# Serial_Keyboard_one.net
KiCad netlist of a schematic drawn in EAGLE
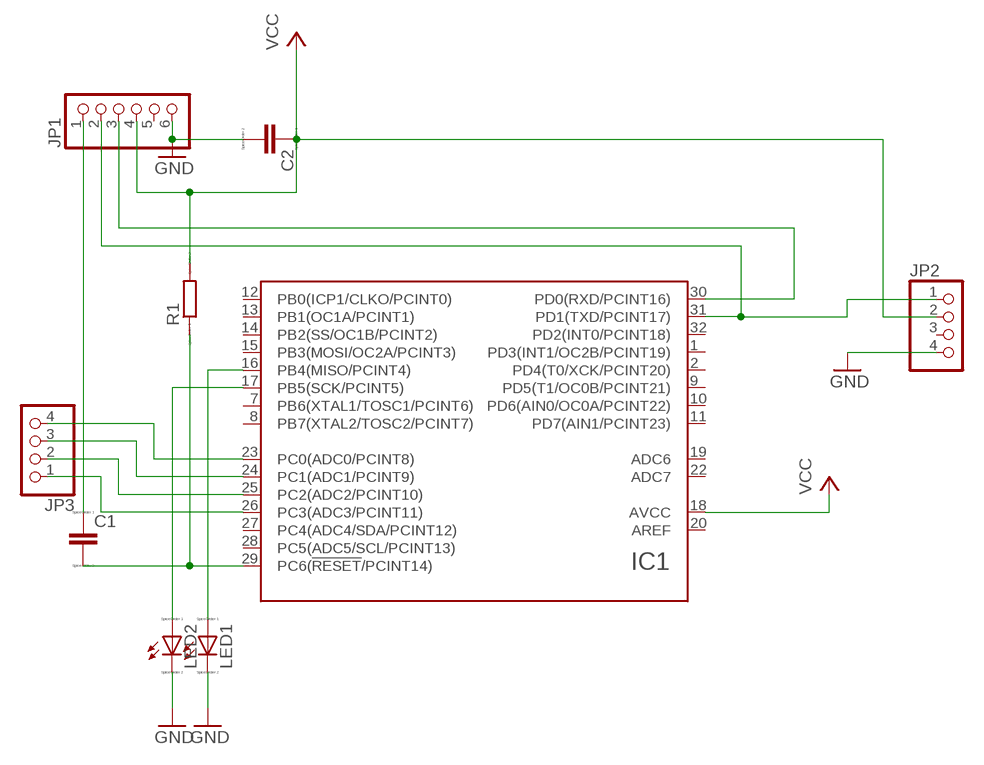
[diagram p0: schematic, sheet 1]

(export (version "E")
  (design (tool "Eeschema 10.0.6"))
  (components
    (comp (ref "C1")
      (value "CC0603")
      (footprint "eagle-import:C0603")
      (libsource (lib "eagle-import") (part "CC0603"))
    )
    (comp (ref "C2")
      (value "CC0603")
      (footprint "eagle-import:C0603")
      (libsource (lib "eagle-import") (part "CC0603"))
    )
    (comp (ref "IC1")
      (value "ATMEGA48/88/168/328-AU")
      (footprint "eagle-import:TQFP32-08")
      (libsource (lib "eagle-import") (part "ATMEGA48/88/168/328-AU"))
    )
    (comp (ref "JP1")
      (value "PINHD-1X6")
      (footprint "eagle-import:1X06")
      (libsource (lib "eagle-import") (part "PINHD-1X6"))
    )
    (comp (ref "JP2")
      (value "PINHD-1X4")
      (footprint "eagle-import:1X04")
      (libsource (lib "eagle-import") (part "PINHD-1X4"))
    )
    (comp (ref "JP3")
      (value "PINHD-1X4")
      (footprint "eagle-import:1X04")
      (libsource (lib "eagle-import") (part "PINHD-1X4"))
    )
    (comp (ref "LED1")
      (value "LED_ELD260")
      (footprint "eagle-import:LED_LD260")
      (libsource (lib "eagle-import") (part "LED_ELD260"))
    )
    (comp (ref "LED2")
      (value "LED_ELD260")
      (footprint "eagle-import:LED_LD260")
      (libsource (lib "eagle-import") (part "LED_ELD260"))
    )
    (comp (ref "R1")
      (value "RR0603")
      (footprint "eagle-import:R0603")
      (libsource (lib "eagle-import") (part "RR0603"))
    )
  )
  (nets
    (net (code "1") (name "GND") (class "Default")
      (node (ref "C2") (pin "2") (pinfunction "2_2") (pintype "passive"))
      (node (ref "JP1") (pin "6") (pinfunction "6_6") (pintype "passive"))
      (node (ref "JP2") (pin "4") (pinfunction "4_4") (pintype "passive"))
      (node (ref "LED1") (pin "K") (pinfunction "C_K") (pintype "passive"))
      (node (ref "LED2") (pin "K") (pinfunction "C_K") (pintype "passive"))
    )
    (net (code "2") (name "Net-(C1-Pad1)") (class "Default")
      (node (ref "C1") (pin "1") (pinfunction "1_1") (pintype "passive"))
      (node (ref "JP1") (pin "1") (pinfunction "1_1") (pintype "passive"))
    )
    (net (code "3") (name "Net-(IC1A-PB4(MISO{slash}PCINT4))") (class "Default")
      (node (ref "IC1") (pin "16") (pinfunction "PB4(MISO/PCINT4)_16") (pintype "bidirectional"))
      (node (ref "LED1") (pin "A") (pinfunction "A_A") (pintype "passive"))
    )
    (net (code "4") (name "Net-(IC1A-PB5(SCK{slash}PCINT5))") (class "Default")
      (node (ref "IC1") (pin "17") (pinfunction "PB5(SCK/PCINT5)_17") (pintype "bidirectional"))
      (node (ref "LED2") (pin "A") (pinfunction "A_A") (pintype "passive"))
    )
    (net (code "5") (name "Net-(IC1A-PC0(ADC0{slash}PCINT8))") (class "Default")
      (node (ref "IC1") (pin "23") (pinfunction "PC0(ADC0/PCINT8)_23") (pintype "bidirectional"))
      (node (ref "JP3") (pin "4") (pinfunction "4_4") (pintype "passive"))
    )
    (net (code "6") (name "Net-(IC1A-PC1(ADC1{slash}PCINT9))") (class "Default")
      (node (ref "IC1") (pin "24") (pinfunction "PC1(ADC1/PCINT9)_24") (pintype "bidirectional"))
      (node (ref "JP3") (pin "3") (pinfunction "3_3") (pintype "passive"))
    )
    (net (code "7") (name "Net-(IC1A-PC2(ADC2{slash}PCINT10))") (class "Default")
      (node (ref "IC1") (pin "25") (pinfunction "PC2(ADC2/PCINT10)_25") (pintype "bidirectional"))
      (node (ref "JP3") (pin "2") (pinfunction "2_2") (pintype "passive"))
    )
    (net (code "8") (name "Net-(IC1A-PC3(ADC3{slash}PCINT11))") (class "Default")
      (node (ref "IC1") (pin "26") (pinfunction "PC3(ADC3/PCINT11)_26") (pintype "bidirectional"))
      (node (ref "JP3") (pin "1") (pinfunction "1_1") (pintype "passive"))
    )
    (net (code "9") (name "Net-(IC1A-PC6(~{RESET}{slash}PCINT14))") (class "Default")
      (node (ref "C1") (pin "2") (pinfunction "2_2") (pintype "passive"))
      (node (ref "IC1") (pin "29") (pinfunction "PC6(~{RESET}/PCINT14)_29") (pintype "bidirectional"))
      (node (ref "R1") (pin "1") (pinfunction "1_1") (pintype "passive"))
    )
    (net (code "10") (name "Net-(IC1A-PD0(RXD{slash}PCINT16))") (class "Default")
      (node (ref "IC1") (pin "30") (pinfunction "PD0(RXD/PCINT16)_30") (pintype "bidirectional"))
      (node (ref "JP1") (pin "3") (pinfunction "3_3") (pintype "passive"))
    )
    (net (code "11") (name "Net-(IC1A-PD1(TXD{slash}PCINT17))") (class "Default")
      (node (ref "IC1") (pin "31") (pinfunction "PD1(TXD/PCINT17)_31") (pintype "bidirectional"))
      (node (ref "JP1") (pin "2") (pinfunction "2_2") (pintype "passive"))
      (node (ref "JP2") (pin "1") (pinfunction "1_1") (pintype "passive"))
    )
    (net (code "12") (name "VCC") (class "Default")
      (node (ref "C2") (pin "1") (pinfunction "1_1") (pintype "passive"))
      (node (ref "IC1") (pin "18") (pinfunction "AVCC_18") (pintype "power_in"))
      (node (ref "JP1") (pin "4") (pinfunction "4_4") (pintype "passive"))
      (node (ref "JP2") (pin "2") (pinfunction "2_2") (pintype "passive"))
      (node (ref "R1") (pin "2") (pinfunction "2_2") (pintype "passive"))
    )
    (net (code "13") (name "unconnected-(IC1A-ADC6-Pad19)") (class "Default")
      (node (ref "IC1") (pin "19") (pinfunction "ADC6_19") (pintype "passive"))
    )
    (net (code "14") (name "unconnected-(IC1A-ADC7-Pad22)") (class "Default")
      (node (ref "IC1") (pin "22") (pinfunction "ADC7_22") (pintype "passive"))
    )
    (net (code "15") (name "unconnected-(IC1A-AREF-Pad20)") (class "Default")
      (node (ref "IC1") (pin "20") (pinfunction "AREF_20") (pintype "passive"))
    )
    (net (code "16") (name "unconnected-(IC1A-PB0(ICP1{slash}CLKO{slash}PCINT0)-Pad12)") (class "Default")
      (node (ref "IC1") (pin "12") (pinfunction "PB0(ICP1/CLKO/PCINT0)_12") (pintype "bidirectional"))
    )
    (net (code "17") (name "unconnected-(IC1A-PB1(OC1A{slash}PCINT1)-Pad13)") (class "Default")
      (node (ref "IC1") (pin "13") (pinfunction "PB1(OC1A/PCINT1)_13") (pintype "bidirectional"))
    )
    (net (code "18") (name "unconnected-(IC1A-PB2(SS{slash}OC1B{slash}PCINT2)-Pad14)") (class "Default")
      (node (ref "IC1") (pin "14") (pinfunction "PB2(SS/OC1B/PCINT2)_14") (pintype "bidirectional"))
    )
    (net (code "19") (name "unconnected-(IC1A-PB3(MOSI{slash}OC2A{slash}PCINT3)-Pad15)") (class "Default")
      (node (ref "IC1") (pin "15") (pinfunction "PB3(MOSI/OC2A/PCINT3)_15") (pintype "bidirectional"))
    )
    (net (code "20") (name "unconnected-(IC1A-PB6(XTAL1{slash}TOSC1{slash}PCINT6)-Pad7)") (class "Default")
      (node (ref "IC1") (pin "7") (pinfunction "PB6(XTAL1/TOSC1/PCINT6)_7") (pintype "bidirectional"))
    )
    (net (code "21") (name "unconnected-(IC1A-PB7(XTAL2{slash}TOSC2{slash}PCINT7)-Pad8)") (class "Default")
      (node (ref "IC1") (pin "8") (pinfunction "PB7(XTAL2/TOSC2/PCINT7)_8") (pintype "bidirectional"))
    )
    (net (code "22") (name "unconnected-(IC1A-PC4(ADC4{slash}SDA{slash}PCINT12)-Pad27)") (class "Default")
      (node (ref "IC1") (pin "27") (pinfunction "PC4(ADC4/SDA/PCINT12)_27") (pintype "bidirectional"))
    )
    (net (code "23") (name "unconnected-(IC1A-PC5(ADC5{slash}SCL{slash}PCINT13)-Pad28)") (class "Default")
      (node (ref "IC1") (pin "28") (pinfunction "PC5(ADC5/SCL/PCINT13)_28") (pintype "bidirectional"))
    )
    (net (code "24") (name "unconnected-(IC1A-PD2(INT0{slash}PCINT18)-Pad32)") (class "Default")
      (node (ref "IC1") (pin "32") (pinfunction "PD2(INT0/PCINT18)_32") (pintype "bidirectional"))
    )
    (net (code "25") (name "unconnected-(IC1A-PD3(INT1{slash}OC2B{slash}PCINT19)-Pad1)") (class "Default")
      (node (ref "IC1") (pin "1") (pinfunction "PD3(INT1/OC2B/PCINT19)_1") (pintype "bidirectional"))
    )
    (net (code "26") (name "unconnected-(IC1A-PD4(T0{slash}XCK{slash}PCINT20)-Pad2)") (class "Default")
      (node (ref "IC1") (pin "2") (pinfunction "PD4(T0/XCK/PCINT20)_2") (pintype "bidirectional"))
    )
    (net (code "27") (name "unconnected-(IC1A-PD5(T1{slash}OC0B{slash}PCINT21)-Pad9)") (class "Default")
      (node (ref "IC1") (pin "9") (pinfunction "PD5(T1/OC0B/PCINT21)_9") (pintype "bidirectional"))
    )
    (net (code "28") (name "unconnected-(IC1A-PD6(AIN0{slash}OC0A{slash}PCINT22)-Pad10)") (class "Default")
      (node (ref "IC1") (pin "10") (pinfunction "PD6(AIN0/OC0A/PCINT22)_10") (pintype "bidirectional"))
    )
    (net (code "29") (name "unconnected-(IC1A-PD7(AIN1{slash}PCINT23)-Pad11)") (class "Default")
      (node (ref "IC1") (pin "11") (pinfunction "PD7(AIN1/PCINT23)_11") (pintype "bidirectional"))
    )
    (net (code "30") (name "unconnected-(JP1-Pad5)") (class "Default")
      (node (ref "JP1") (pin "5") (pinfunction "5_5") (pintype "passive"))
    )
    (net (code "31") (name "unconnected-(JP2-Pad3)") (class "Default")
      (node (ref "JP2") (pin "3") (pinfunction "3_3") (pintype "passive"))
    )
  )
)
